# 07_Connector.net
KiCad netlist of a schematic drawn in Altium Designer
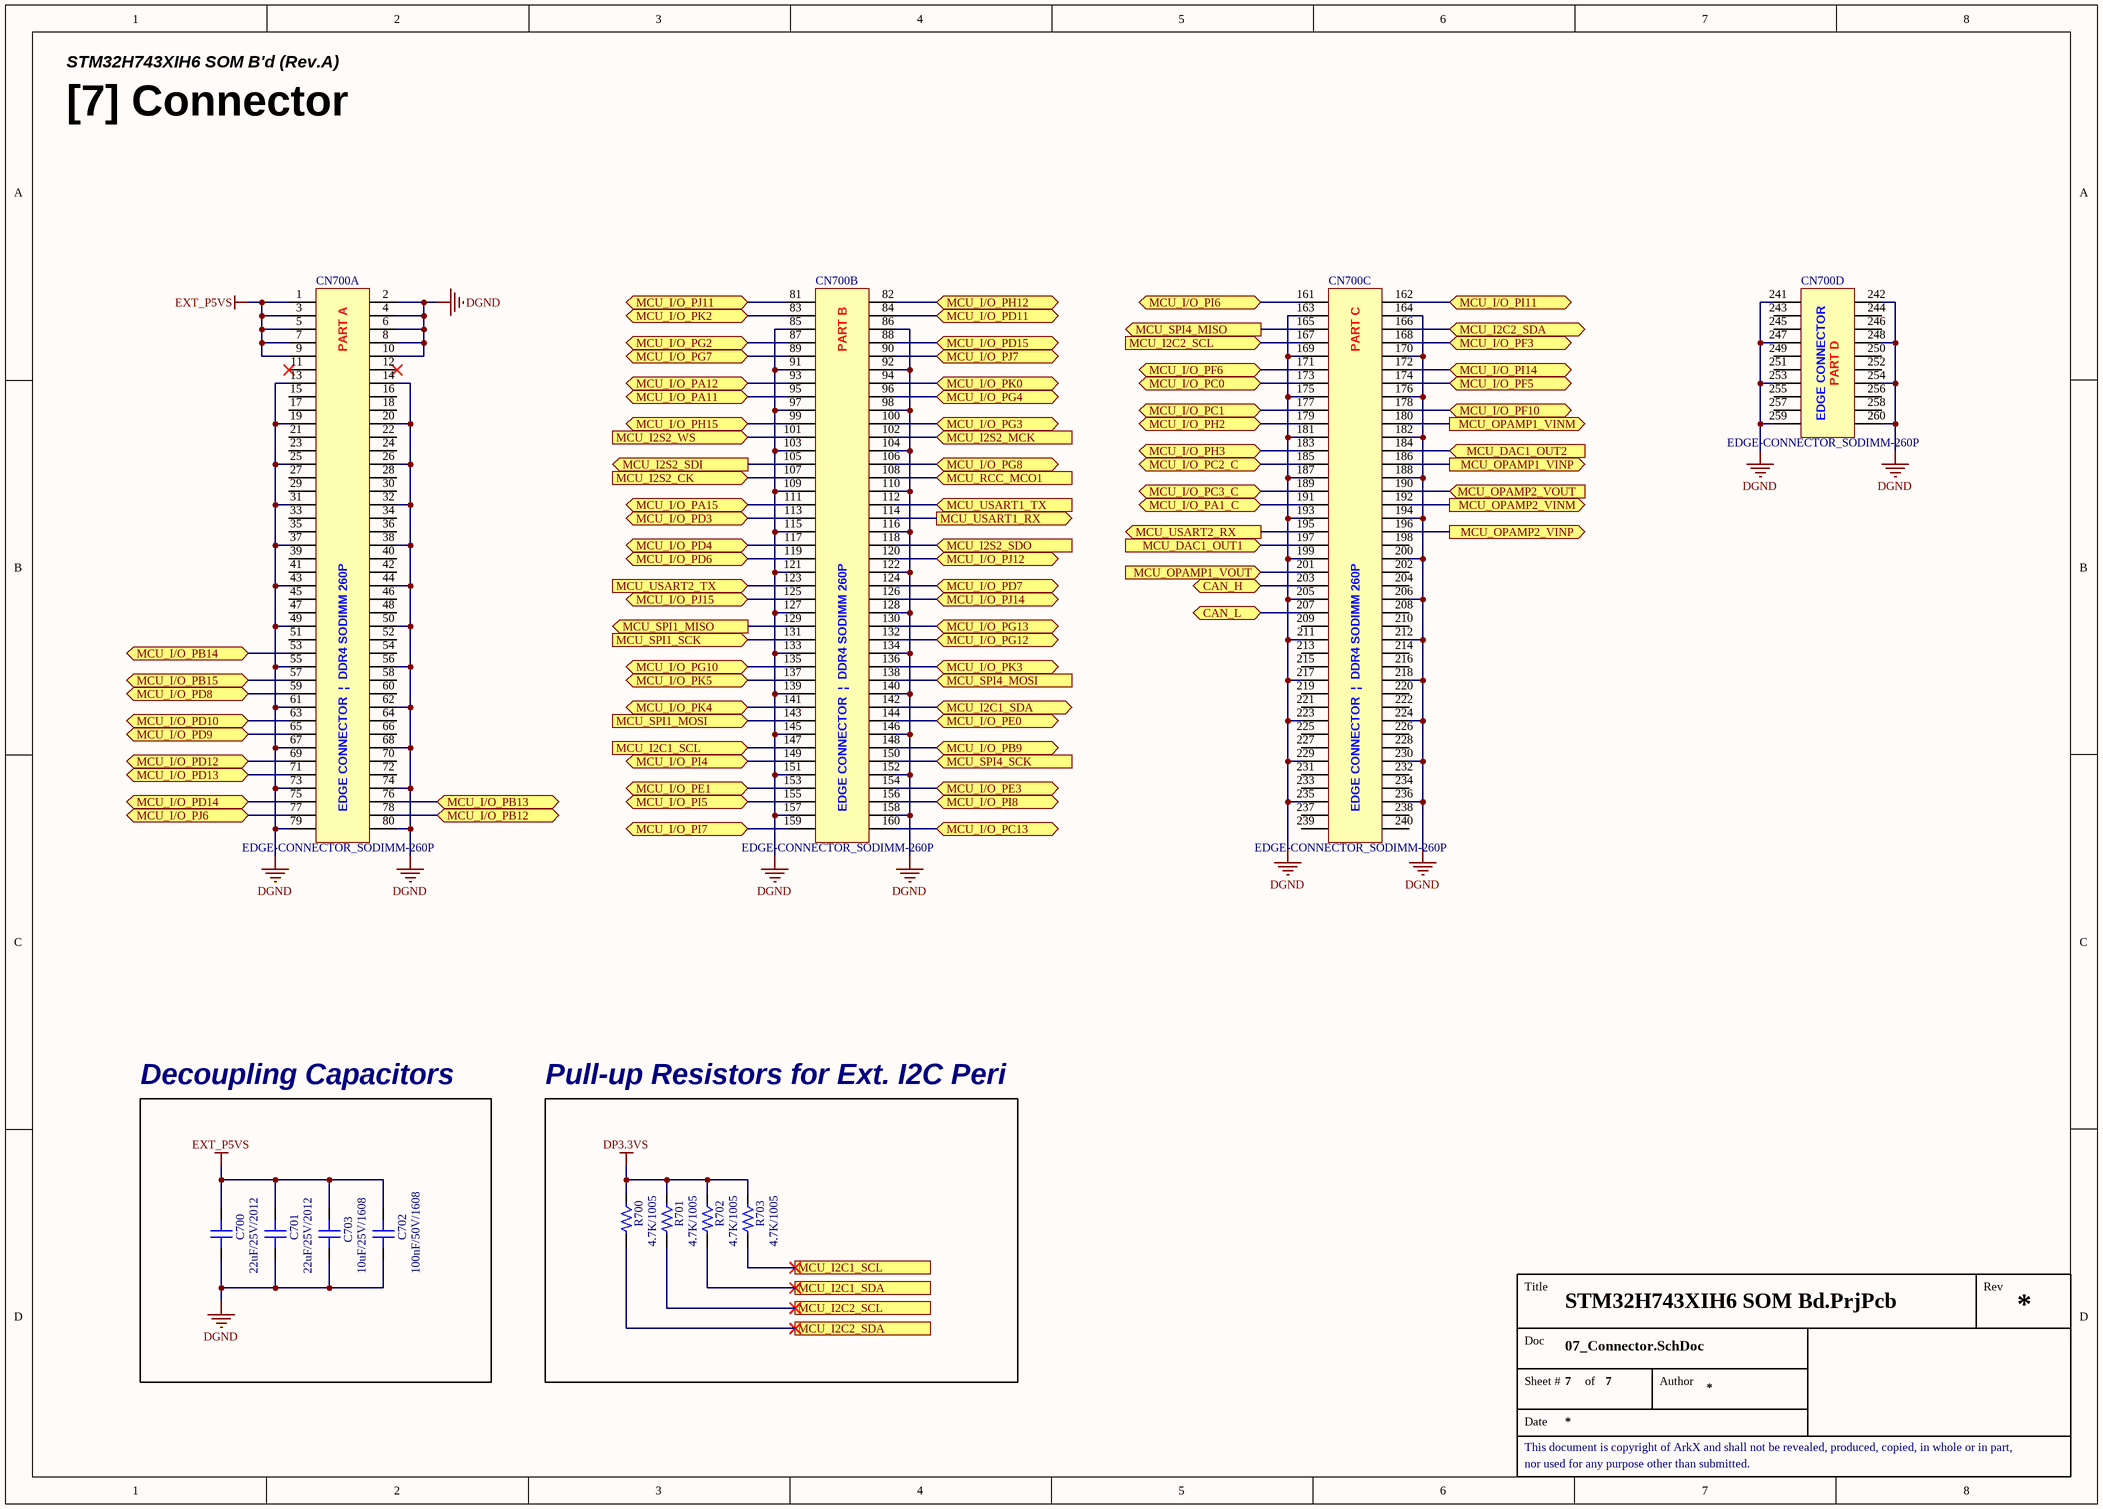
[diagram p0: 07_Connector.SchDoc]

(export (version "E")
  (design (tool "Eeschema 10.0.6"))
  (components
    (comp (ref "C700")
      (value "22uF/25V/2012")
      (footprint "CAP 2012 (0805_INCH)")
      (description "Ceramic CAP_22uF/25V/2012")
      (fields (field (name "LCSC PART #") "C45783"))
      (libsource (lib "Arkx") (part "CAP_22uF/25V/2012"))
    )
    (comp (ref "C701")
      (value "22uF/25V/2012")
      (footprint "CAP 2012 (0805_INCH)")
      (description "Ceramic CAP_22uF/25V/2012")
      (fields (field (name "LCSC PART #") "C45783"))
      (libsource (lib "Arkx") (part "CAP_22uF/25V/2012"))
    )
    (comp (ref "C702")
      (value "100nF/50V/1608")
      (footprint "CAP 1608 (0603_INCH)")
      (description "Ceramic CAP_100nF/50V/1608")
      (fields (field (name "LCSC PART #") "C14663"))
      (libsource (lib "Arkx") (part "CAP_100nF/50V/1608"))
    )
    (comp (ref "C703")
      (value "10uF/25V/1608")
      (footprint "CAP 1608 (0603_INCH)")
      (description "Ceramic CAP_10uF/25V/1608")
      (fields (field (name "LCSC PART #") "C96446"))
      (libsource (lib "Arkx") (part "CAP_10uF/25V/1608"))
    )
    (comp (ref "CN700")
      (value "EDGE-CONNECTOR_SODIMM-260P")
      (footprint "CON_EDGE-CONNECTOR_DDR4-SODIMM-260P")
      (description "EDGE-CONNECTOR_DDR4-SODIMM-260P")
      (fields (field (name "MATING PART NUMBER") "2309409-1"))
      (libsource (lib "Arkx") (part "CON_EDGE-CONNECTOR_DDR4-SODIMM-260P"))
    )
    (comp (ref "R700")
      (value "4.7K/1005")
      (footprint "RES 1005 (0402_inch)")
      (description "RES_4.7K/1005/62.5mW")
      (fields (field (name "LCSC PART #") "C25900"))
      (libsource (lib "Arkx") (part "RES_4.7K/1005/62.5mW"))
    )
    (comp (ref "R701")
      (value "4.7K/1005")
      (footprint "RES 1005 (0402_inch)")
      (description "RES_4.7K/1005/62.5mW")
      (fields (field (name "LCSC PART #") "C25900"))
      (libsource (lib "Arkx") (part "RES_4.7K/1005/62.5mW"))
    )
    (comp (ref "R702")
      (value "4.7K/1005")
      (footprint "RES 1005 (0402_inch)")
      (description "RES_4.7K/1005/62.5mW")
      (fields (field (name "LCSC PART #") "C25900"))
      (libsource (lib "Arkx") (part "RES_4.7K/1005/62.5mW"))
    )
    (comp (ref "R703")
      (value "4.7K/1005")
      (footprint "RES 1005 (0402_inch)")
      (description "RES_4.7K/1005/62.5mW")
      (fields (field (name "LCSC PART #") "C25900"))
      (libsource (lib "Arkx") (part "RES_4.7K/1005/62.5mW"))
    )
  )
  (nets
    (net (code "1") (name "/CAN_H") (class "Default")
      (node (ref "CN700") (pin "203") (pinfunction "203_203") (pintype "passive"))
    )
    (net (code "2") (name "/CAN_L") (class "Default")
      (node (ref "CN700") (pin "207") (pinfunction "207_207") (pintype "passive"))
    )
    (net (code "3") (name "/MCU_DAC1_OUT1") (class "Default")
      (node (ref "CN700") (pin "197") (pinfunction "197_197") (pintype "passive"))
    )
    (net (code "4") (name "/MCU_DAC1_OUT2") (class "Default")
      (node (ref "CN700") (pin "184") (pinfunction "184_184") (pintype "passive"))
    )
    (net (code "5") (name "/MCU_I2C1_SCL") (class "Default")
      (node (ref "CN700") (pin "147") (pinfunction "147_147") (pintype "passive"))
      (node (ref "R703") (pin "2") (pinfunction "2_2") (pintype "passive"))
    )
    (net (code "6") (name "/MCU_I2C1_SDA") (class "Default")
      (node (ref "CN700") (pin "142") (pinfunction "142_142") (pintype "passive"))
      (node (ref "R702") (pin "2") (pinfunction "2_2") (pintype "passive"))
    )
    (net (code "7") (name "/MCU_I2C2_SCL") (class "Default")
      (node (ref "CN700") (pin "167") (pinfunction "167_167") (pintype "passive"))
      (node (ref "R701") (pin "2") (pinfunction "2_2") (pintype "passive"))
    )
    (net (code "8") (name "/MCU_I2C2_SDA") (class "Default")
      (node (ref "CN700") (pin "166") (pinfunction "166_166") (pintype "passive"))
      (node (ref "R700") (pin "2") (pinfunction "2_2") (pintype "passive"))
    )
    (net (code "9") (name "/MCU_I2S2_CK") (class "Default")
      (node (ref "CN700") (pin "107") (pinfunction "107_107") (pintype "passive"))
    )
    (net (code "10") (name "/MCU_I2S2_MCK") (class "Default")
      (node (ref "CN700") (pin "102") (pinfunction "102_102") (pintype "passive"))
    )
    (net (code "11") (name "/MCU_I2S2_SDI") (class "Default")
      (node (ref "CN700") (pin "105") (pinfunction "105_105") (pintype "passive"))
    )
    (net (code "12") (name "/MCU_I2S2_SDO") (class "Default")
      (node (ref "CN700") (pin "118") (pinfunction "118_118") (pintype "passive"))
    )
    (net (code "13") (name "/MCU_I2S2_WS") (class "Default")
      (node (ref "CN700") (pin "101") (pinfunction "101_101") (pintype "passive"))
    )
    (net (code "14") (name "/MCU_I{slash}O_PA1_C") (class "Default")
      (node (ref "CN700") (pin "191") (pinfunction "191_191") (pintype "passive"))
    )
    (net (code "15") (name "/MCU_I{slash}O_PA11") (class "Default")
      (node (ref "CN700") (pin "95") (pinfunction "95_95") (pintype "passive"))
    )
    (net (code "16") (name "/MCU_I{slash}O_PA12") (class "Default")
      (node (ref "CN700") (pin "93") (pinfunction "93_93") (pintype "passive"))
    )
    (net (code "17") (name "/MCU_I{slash}O_PA15") (class "Default")
      (node (ref "CN700") (pin "111") (pinfunction "111_111") (pintype "passive"))
    )
    (net (code "18") (name "/MCU_I{slash}O_PB9") (class "Default")
      (node (ref "CN700") (pin "148") (pinfunction "148_148") (pintype "passive"))
    )
    (net (code "19") (name "/MCU_I{slash}O_PB12") (class "Default")
      (node (ref "CN700") (pin "78") (pinfunction "78_78") (pintype "passive"))
    )
    (net (code "20") (name "/MCU_I{slash}O_PB13") (class "Default")
      (node (ref "CN700") (pin "76") (pinfunction "76_76") (pintype "passive"))
    )
    (net (code "21") (name "/MCU_I{slash}O_PB14") (class "Default")
      (node (ref "CN700") (pin "53") (pinfunction "53_53") (pintype "passive"))
    )
    (net (code "22") (name "/MCU_I{slash}O_PB15") (class "Default")
      (node (ref "CN700") (pin "57") (pinfunction "57_57") (pintype "passive"))
    )
    (net (code "23") (name "/MCU_I{slash}O_PC0") (class "Default")
      (node (ref "CN700") (pin "173") (pinfunction "173_173") (pintype "passive"))
    )
    (net (code "24") (name "/MCU_I{slash}O_PC1") (class "Default")
      (node (ref "CN700") (pin "177") (pinfunction "177_177") (pintype "passive"))
    )
    (net (code "25") (name "/MCU_I{slash}O_PC2_C") (class "Default")
      (node (ref "CN700") (pin "185") (pinfunction "185_185") (pintype "passive"))
    )
    (net (code "26") (name "/MCU_I{slash}O_PC3_C") (class "Default")
      (node (ref "CN700") (pin "189") (pinfunction "189_189") (pintype "passive"))
    )
    (net (code "27") (name "/MCU_I{slash}O_PC13") (class "Default")
      (node (ref "CN700") (pin "160") (pinfunction "160_160") (pintype "passive"))
    )
    (net (code "28") (name "/MCU_I{slash}O_PD3") (class "Default")
      (node (ref "CN700") (pin "113") (pinfunction "113_113") (pintype "passive"))
    )
    (net (code "29") (name "/MCU_I{slash}O_PD4") (class "Default")
      (node (ref "CN700") (pin "117") (pinfunction "117_117") (pintype "passive"))
    )
    (net (code "30") (name "/MCU_I{slash}O_PD6") (class "Default")
      (node (ref "CN700") (pin "119") (pinfunction "119_119") (pintype "passive"))
    )
    (net (code "31") (name "/MCU_I{slash}O_PD7") (class "Default")
      (node (ref "CN700") (pin "124") (pinfunction "124_124") (pintype "passive"))
    )
    (net (code "32") (name "/MCU_I{slash}O_PD8") (class "Default")
      (node (ref "CN700") (pin "59") (pinfunction "59_59") (pintype "passive"))
    )
    (net (code "33") (name "/MCU_I{slash}O_PD9") (class "Default")
      (node (ref "CN700") (pin "65") (pinfunction "65_65") (pintype "passive"))
    )
    (net (code "34") (name "/MCU_I{slash}O_PD10") (class "Default")
      (node (ref "CN700") (pin "63") (pinfunction "63_63") (pintype "passive"))
    )
    (net (code "35") (name "/MCU_I{slash}O_PD11") (class "Default")
      (node (ref "CN700") (pin "84") (pinfunction "84_84") (pintype "passive"))
    )
    (net (code "36") (name "/MCU_I{slash}O_PD12") (class "Default")
      (node (ref "CN700") (pin "69") (pinfunction "69_69") (pintype "passive"))
    )
    (net (code "37") (name "/MCU_I{slash}O_PD13") (class "Default")
      (node (ref "CN700") (pin "71") (pinfunction "71_71") (pintype "passive"))
    )
    (net (code "38") (name "/MCU_I{slash}O_PD14") (class "Default")
      (node (ref "CN700") (pin "75") (pinfunction "75_75") (pintype "passive"))
    )
    (net (code "39") (name "/MCU_I{slash}O_PD15") (class "Default")
      (node (ref "CN700") (pin "88") (pinfunction "88_88") (pintype "passive"))
    )
    (net (code "40") (name "/MCU_I{slash}O_PE0") (class "Default")
      (node (ref "CN700") (pin "144") (pinfunction "144_144") (pintype "passive"))
    )
    (net (code "41") (name "/MCU_I{slash}O_PE1") (class "Default")
      (node (ref "CN700") (pin "153") (pinfunction "153_153") (pintype "passive"))
    )
    (net (code "42") (name "/MCU_I{slash}O_PE3") (class "Default")
      (node (ref "CN700") (pin "154") (pinfunction "154_154") (pintype "passive"))
    )
    (net (code "43") (name "/MCU_I{slash}O_PF3") (class "Default")
      (node (ref "CN700") (pin "168") (pinfunction "168_168") (pintype "passive"))
    )
    (net (code "44") (name "/MCU_I{slash}O_PF5") (class "Default")
      (node (ref "CN700") (pin "174") (pinfunction "174_174") (pintype "passive"))
    )
    (net (code "45") (name "/MCU_I{slash}O_PF6") (class "Default")
      (node (ref "CN700") (pin "171") (pinfunction "171_171") (pintype "passive"))
    )
    (net (code "46") (name "/MCU_I{slash}O_PF10") (class "Default")
      (node (ref "CN700") (pin "178") (pinfunction "178_178") (pintype "passive"))
    )
    (net (code "47") (name "/MCU_I{slash}O_PG2") (class "Default")
      (node (ref "CN700") (pin "87") (pinfunction "87_87") (pintype "passive"))
    )
    (net (code "48") (name "/MCU_I{slash}O_PG3") (class "Default")
      (node (ref "CN700") (pin "100") (pinfunction "100_100") (pintype "passive"))
    )
    (net (code "49") (name "/MCU_I{slash}O_PG4") (class "Default")
      (node (ref "CN700") (pin "96") (pinfunction "96_96") (pintype "passive"))
    )
    (net (code "50") (name "/MCU_I{slash}O_PG7") (class "Default")
      (node (ref "CN700") (pin "89") (pinfunction "89_89") (pintype "passive"))
    )
    (net (code "51") (name "/MCU_I{slash}O_PG8") (class "Default")
      (node (ref "CN700") (pin "106") (pinfunction "106_106") (pintype "passive"))
    )
    (net (code "52") (name "/MCU_I{slash}O_PG10") (class "Default")
      (node (ref "CN700") (pin "135") (pinfunction "135_135") (pintype "passive"))
    )
    (net (code "53") (name "/MCU_I{slash}O_PG12") (class "Default")
      (node (ref "CN700") (pin "132") (pinfunction "132_132") (pintype "passive"))
    )
    (net (code "54") (name "/MCU_I{slash}O_PG13") (class "Default")
      (node (ref "CN700") (pin "130") (pinfunction "130_130") (pintype "passive"))
    )
    (net (code "55") (name "/MCU_I{slash}O_PH2") (class "Default")
      (node (ref "CN700") (pin "179") (pinfunction "179_179") (pintype "passive"))
    )
    (net (code "56") (name "/MCU_I{slash}O_PH3") (class "Default")
      (node (ref "CN700") (pin "183") (pinfunction "183_183") (pintype "passive"))
    )
    (net (code "57") (name "/MCU_I{slash}O_PH12") (class "Default")
      (node (ref "CN700") (pin "82") (pinfunction "82_82") (pintype "passive"))
    )
    (net (code "58") (name "/MCU_I{slash}O_PH15") (class "Default")
      (node (ref "CN700") (pin "99") (pinfunction "99_99") (pintype "passive"))
    )
    (net (code "59") (name "/MCU_I{slash}O_PI4") (class "Default")
      (node (ref "CN700") (pin "149") (pinfunction "149_149") (pintype "passive"))
    )
    (net (code "60") (name "/MCU_I{slash}O_PI5") (class "Default")
      (node (ref "CN700") (pin "155") (pinfunction "155_155") (pintype "passive"))
    )
    (net (code "61") (name "/MCU_I{slash}O_PI6") (class "Default")
      (node (ref "CN700") (pin "161") (pinfunction "161_161") (pintype "passive"))
    )
    (net (code "62") (name "/MCU_I{slash}O_PI7") (class "Default")
      (node (ref "CN700") (pin "159") (pinfunction "159_159") (pintype "passive"))
    )
    (net (code "63") (name "/MCU_I{slash}O_PI8") (class "Default")
      (node (ref "CN700") (pin "156") (pinfunction "156_156") (pintype "passive"))
    )
    (net (code "64") (name "/MCU_I{slash}O_PI11") (class "Default")
      (node (ref "CN700") (pin "162") (pinfunction "162_162") (pintype "passive"))
    )
    (net (code "65") (name "/MCU_I{slash}O_PI14") (class "Default")
      (node (ref "CN700") (pin "172") (pinfunction "172_172") (pintype "passive"))
    )
    (net (code "66") (name "/MCU_I{slash}O_PJ6") (class "Default")
      (node (ref "CN700") (pin "77") (pinfunction "77_77") (pintype "passive"))
    )
    (net (code "67") (name "/MCU_I{slash}O_PJ7") (class "Default")
      (node (ref "CN700") (pin "90") (pinfunction "90_90") (pintype "passive"))
    )
    (net (code "68") (name "/MCU_I{slash}O_PJ11") (class "Default")
      (node (ref "CN700") (pin "81") (pinfunction "81_81") (pintype "passive"))
    )
    (net (code "69") (name "/MCU_I{slash}O_PJ12") (class "Default")
      (node (ref "CN700") (pin "120") (pinfunction "120_120") (pintype "passive"))
    )
    (net (code "70") (name "/MCU_I{slash}O_PJ14") (class "Default")
      (node (ref "CN700") (pin "126") (pinfunction "126_126") (pintype "passive"))
    )
    (net (code "71") (name "/MCU_I{slash}O_PJ15") (class "Default")
      (node (ref "CN700") (pin "125") (pinfunction "125_125") (pintype "passive"))
    )
    (net (code "72") (name "/MCU_I{slash}O_PK0") (class "Default")
      (node (ref "CN700") (pin "94") (pinfunction "94_94") (pintype "passive"))
    )
    (net (code "73") (name "/MCU_I{slash}O_PK2") (class "Default")
      (node (ref "CN700") (pin "83") (pinfunction "83_83") (pintype "passive"))
    )
    (net (code "74") (name "/MCU_I{slash}O_PK3") (class "Default")
      (node (ref "CN700") (pin "136") (pinfunction "136_136") (pintype "passive"))
    )
    (net (code "75") (name "/MCU_I{slash}O_PK4") (class "Default")
      (node (ref "CN700") (pin "141") (pinfunction "141_141") (pintype "passive"))
    )
    (net (code "76") (name "/MCU_I{slash}O_PK5") (class "Default")
      (node (ref "CN700") (pin "137") (pinfunction "137_137") (pintype "passive"))
    )
    (net (code "77") (name "/MCU_OPAMP1_VINM") (class "Default")
      (node (ref "CN700") (pin "180") (pinfunction "180_180") (pintype "passive"))
    )
    (net (code "78") (name "/MCU_OPAMP1_VINP") (class "Default")
      (node (ref "CN700") (pin "186") (pinfunction "186_186") (pintype "passive"))
    )
    (net (code "79") (name "/MCU_OPAMP1_VOUT") (class "Default")
      (node (ref "CN700") (pin "201") (pinfunction "201_201") (pintype "passive"))
    )
    (net (code "80") (name "/MCU_OPAMP2_VINM") (class "Default")
      (node (ref "CN700") (pin "192") (pinfunction "192_192") (pintype "passive"))
    )
    (net (code "81") (name "/MCU_OPAMP2_VINP") (class "Default")
      (node (ref "CN700") (pin "196") (pinfunction "196_196") (pintype "passive"))
    )
    (net (code "82") (name "/MCU_OPAMP2_VOUT") (class "Default")
      (node (ref "CN700") (pin "190") (pinfunction "190_190") (pintype "passive"))
    )
    (net (code "83") (name "/MCU_RCC_MCO1") (class "Default")
      (node (ref "CN700") (pin "108") (pinfunction "108_108") (pintype "passive"))
    )
    (net (code "84") (name "/MCU_SPI1_MISO") (class "Default")
      (node (ref "CN700") (pin "129") (pinfunction "129_129") (pintype "passive"))
    )
    (net (code "85") (name "/MCU_SPI1_MOSI") (class "Default")
      (node (ref "CN700") (pin "143") (pinfunction "143_143") (pintype "passive"))
    )
    (net (code "86") (name "/MCU_SPI1_SCK") (class "Default")
      (node (ref "CN700") (pin "131") (pinfunction "131_131") (pintype "passive"))
    )
    (net (code "87") (name "/MCU_SPI4_MISO") (class "Default")
      (node (ref "CN700") (pin "165") (pinfunction "165_165") (pintype "passive"))
    )
    (net (code "88") (name "/MCU_SPI4_MOSI") (class "Default")
      (node (ref "CN700") (pin "138") (pinfunction "138_138") (pintype "passive"))
    )
    (net (code "89") (name "/MCU_SPI4_SCK") (class "Default")
      (node (ref "CN700") (pin "150") (pinfunction "150_150") (pintype "passive"))
    )
    (net (code "90") (name "/MCU_USART1_RX") (class "Default")
      (node (ref "CN700") (pin "114") (pinfunction "114_114") (pintype "passive"))
    )
    (net (code "91") (name "/MCU_USART1_TX") (class "Default")
      (node (ref "CN700") (pin "112") (pinfunction "112_112") (pintype "passive"))
    )
    (net (code "92") (name "/MCU_USART2_RX") (class "Default")
      (node (ref "CN700") (pin "195") (pinfunction "195_195") (pintype "passive"))
    )
    (net (code "93") (name "/MCU_USART2_TX") (class "Default")
      (node (ref "CN700") (pin "123") (pinfunction "123_123") (pintype "passive"))
    )
    (net (code "94") (name "DGND") (class "Default")
      (node (ref "C700") (pin "1") (pinfunction "1_1") (pintype "passive"))
      (node (ref "C701") (pin "1") (pinfunction "1_1") (pintype "passive"))
      (node (ref "C702") (pin "1") (pinfunction "1_1") (pintype "passive"))
      (node (ref "C703") (pin "1") (pinfunction "1_1") (pintype "passive"))
      (node (ref "CN700") (pin "10") (pinfunction "10_10") (pintype "passive"))
      (node (ref "CN700") (pin "103") (pinfunction "103_103") (pintype "passive"))
      (node (ref "CN700") (pin "104") (pinfunction "104_104") (pintype "passive"))
      (node (ref "CN700") (pin "109") (pinfunction "109_109") (pintype "passive"))
      (node (ref "CN700") (pin "110") (pinfunction "110_110") (pintype "passive"))
      (node (ref "CN700") (pin "115") (pinfunction "115_115") (pintype "passive"))
      (node (ref "CN700") (pin "116") (pinfunction "116_116") (pintype "passive"))
      (node (ref "CN700") (pin "121") (pinfunction "121_121") (pintype "passive"))
      (node (ref "CN700") (pin "122") (pinfunction "122_122") (pintype "passive"))
      (node (ref "CN700") (pin "127") (pinfunction "127_127") (pintype "passive"))
      (node (ref "CN700") (pin "128") (pinfunction "128_128") (pintype "passive"))
      (node (ref "CN700") (pin "13") (pinfunction "13_13") (pintype "passive"))
      (node (ref "CN700") (pin "133") (pinfunction "133_133") (pintype "passive"))
      (node (ref "CN700") (pin "134") (pinfunction "134_134") (pintype "passive"))
      (node (ref "CN700") (pin "139") (pinfunction "139_139") (pintype "passive"))
      (node (ref "CN700") (pin "14") (pinfunction "14_14") (pintype "passive"))
      (node (ref "CN700") (pin "140") (pinfunction "140_140") (pintype "passive"))
      (node (ref "CN700") (pin "145") (pinfunction "145_145") (pintype "passive"))
      (node (ref "CN700") (pin "146") (pinfunction "146_146") (pintype "passive"))
      (node (ref "CN700") (pin "151") (pinfunction "151_151") (pintype "passive"))
      (node (ref "CN700") (pin "152") (pinfunction "152_152") (pintype "passive"))
      (node (ref "CN700") (pin "157") (pinfunction "157_157") (pintype "passive"))
      (node (ref "CN700") (pin "158") (pinfunction "158_158") (pintype "passive"))
      (node (ref "CN700") (pin "163") (pinfunction "163_163") (pintype "passive"))
      (node (ref "CN700") (pin "164") (pinfunction "164_164") (pintype "passive"))
      (node (ref "CN700") (pin "169") (pinfunction "169_169") (pintype "passive"))
      (node (ref "CN700") (pin "170") (pinfunction "170_170") (pintype "passive"))
      (node (ref "CN700") (pin "175") (pinfunction "175_175") (pintype "passive"))
      (node (ref "CN700") (pin "176") (pinfunction "176_176") (pintype "passive"))
      (node (ref "CN700") (pin "181") (pinfunction "181_181") (pintype "passive"))
      (node (ref "CN700") (pin "182") (pinfunction "182_182") (pintype "passive"))
      (node (ref "CN700") (pin "187") (pinfunction "187_187") (pintype "passive"))
      (node (ref "CN700") (pin "188") (pinfunction "188_188") (pintype "passive"))
      (node (ref "CN700") (pin "19") (pinfunction "19_19") (pintype "passive"))
      (node (ref "CN700") (pin "193") (pinfunction "193_193") (pintype "passive"))
      (node (ref "CN700") (pin "194") (pinfunction "194_194") (pintype "passive"))
      (node (ref "CN700") (pin "199") (pinfunction "199_199") (pintype "passive"))
      (node (ref "CN700") (pin "2") (pinfunction "2_2") (pintype "passive"))
      (node (ref "CN700") (pin "20") (pinfunction "20_20") (pintype "passive"))
      (node (ref "CN700") (pin "200") (pinfunction "200_200") (pintype "passive"))
      (node (ref "CN700") (pin "205") (pinfunction "205_205") (pintype "passive"))
      (node (ref "CN700") (pin "206") (pinfunction "206_206") (pintype "passive"))
      (node (ref "CN700") (pin "211") (pinfunction "211_211") (pintype "passive"))
      (node (ref "CN700") (pin "212") (pinfunction "212_212") (pintype "passive"))
      (node (ref "CN700") (pin "217") (pinfunction "217_217") (pintype "passive"))
      (node (ref "CN700") (pin "218") (pinfunction "218_218") (pintype "passive"))
      (node (ref "CN700") (pin "223") (pinfunction "223_223") (pintype "passive"))
      (node (ref "CN700") (pin "224") (pinfunction "224_224") (pintype "passive"))
      (node (ref "CN700") (pin "229") (pinfunction "229_229") (pintype "passive"))
      (node (ref "CN700") (pin "230") (pinfunction "230_230") (pintype "passive"))
      (node (ref "CN700") (pin "235") (pinfunction "235_235") (pintype "passive"))
      (node (ref "CN700") (pin "236") (pinfunction "236_236") (pintype "passive"))
      (node (ref "CN700") (pin "241") (pinfunction "241_241") (pintype "passive"))
      (node (ref "CN700") (pin "242") (pinfunction "242_242") (pintype "passive"))
      (node (ref "CN700") (pin "247") (pinfunction "247_247") (pintype "passive"))
      (node (ref "CN700") (pin "248") (pinfunction "248_248") (pintype "passive"))
      (node (ref "CN700") (pin "25") (pinfunction "25_25") (pintype "passive"))
      (node (ref "CN700") (pin "253") (pinfunction "253_253") (pintype "passive"))
      (node (ref "CN700") (pin "254") (pinfunction "254_254") (pintype "passive"))
      (node (ref "CN700") (pin "259") (pinfunction "259_259") (pintype "passive"))
      (node (ref "CN700") (pin "26") (pinfunction "26_26") (pintype "passive"))
      (node (ref "CN700") (pin "260") (pinfunction "260_260") (pintype "passive"))
      (node (ref "CN700") (pin "31") (pinfunction "31_31") (pintype "passive"))
      (node (ref "CN700") (pin "32") (pinfunction "32_32") (pintype "passive"))
      (node (ref "CN700") (pin "37") (pinfunction "37_37") (pintype "passive"))
      (node (ref "CN700") (pin "38") (pinfunction "38_38") (pintype "passive"))
      (node (ref "CN700") (pin "4") (pinfunction "4_4") (pintype "passive"))
      (node (ref "CN700") (pin "43") (pinfunction "43_43") (pintype "passive"))
      (node (ref "CN700") (pin "44") (pinfunction "44_44") (pintype "passive"))
      (node (ref "CN700") (pin "49") (pinfunction "49_49") (pintype "passive"))
      (node (ref "CN700") (pin "50") (pinfunction "50_50") (pintype "passive"))
      (node (ref "CN700") (pin "55") (pinfunction "55_55") (pintype "passive"))
      (node (ref "CN700") (pin "56") (pinfunction "56_56") (pintype "passive"))
      (node (ref "CN700") (pin "6") (pinfunction "6_6") (pintype "passive"))
      (node (ref "CN700") (pin "61") (pinfunction "61_61") (pintype "passive"))
      (node (ref "CN700") (pin "62") (pinfunction "62_62") (pintype "passive"))
      (node (ref "CN700") (pin "67") (pinfunction "67_67") (pintype "passive"))
      (node (ref "CN700") (pin "68") (pinfunction "68_68") (pintype "passive"))
      (node (ref "CN700") (pin "73") (pinfunction "73_73") (pintype "passive"))
      (node (ref "CN700") (pin "74") (pinfunction "74_74") (pintype "passive"))
      (node (ref "CN700") (pin "79") (pinfunction "79_79") (pintype "passive"))
      (node (ref "CN700") (pin "8") (pinfunction "8_8") (pintype "passive"))
      (node (ref "CN700") (pin "80") (pinfunction "80_80") (pintype "passive"))
      (node (ref "CN700") (pin "85") (pinfunction "85_85") (pintype "passive"))
      (node (ref "CN700") (pin "86") (pinfunction "86_86") (pintype "passive"))
      (node (ref "CN700") (pin "91") (pinfunction "91_91") (pintype "passive"))
      (node (ref "CN700") (pin "92") (pinfunction "92_92") (pintype "passive"))
      (node (ref "CN700") (pin "97") (pinfunction "97_97") (pintype "passive"))
      (node (ref "CN700") (pin "98") (pinfunction "98_98") (pintype "passive"))
    )
    (net (code "95") (name "DP3.3VS") (class "Default")
      (node (ref "R700") (pin "1") (pinfunction "1_1") (pintype "passive"))
      (node (ref "R701") (pin "1") (pinfunction "1_1") (pintype "passive"))
      (node (ref "R702") (pin "1") (pinfunction "1_1") (pintype "passive"))
      (node (ref "R703") (pin "1") (pinfunction "1_1") (pintype "passive"))
    )
    (net (code "96") (name "EXT_P5VS") (class "Default")
      (node (ref "C700") (pin "2") (pinfunction "2_2") (pintype "passive"))
      (node (ref "C701") (pin "2") (pinfunction "2_2") (pintype "passive"))
      (node (ref "C702") (pin "2") (pinfunction "2_2") (pintype "passive"))
      (node (ref "C703") (pin "2") (pinfunction "2_2") (pintype "passive"))
      (node (ref "CN700") (pin "1") (pinfunction "1_1") (pintype "passive"))
      (node (ref "CN700") (pin "3") (pinfunction "3_3") (pintype "passive"))
      (node (ref "CN700") (pin "5") (pinfunction "5_5") (pintype "passive"))
      (node (ref "CN700") (pin "7") (pinfunction "7_7") (pintype "passive"))
      (node (ref "CN700") (pin "9") (pinfunction "9_9") (pintype "passive"))
    )
    (net (code "97") (name "unconnected-(CN700-Pad11)") (class "Default")
      (node (ref "CN700") (pin "11") (pinfunction "11_11") (pintype "passive+no_connect"))
    )
    (net (code "98") (name "unconnected-(CN700-Pad12)") (class "Default")
      (node (ref "CN700") (pin "12") (pinfunction "12_12") (pintype "passive+no_connect"))
    )
    (net (code "99") (name "unconnected-(CN700-Pad15)") (class "Default")
      (node (ref "CN700") (pin "15") (pinfunction "15_15") (pintype "passive"))
    )
    (net (code "100") (name "unconnected-(CN700-Pad16)") (class "Default")
      (node (ref "CN700") (pin "16") (pinfunction "16_16") (pintype "passive"))
    )
    (net (code "101") (name "unconnected-(CN700-Pad17)") (class "Default")
      (node (ref "CN700") (pin "17") (pinfunction "17_17") (pintype "passive"))
    )
    (net (code "102") (name "unconnected-(CN700-Pad18)") (class "Default")
      (node (ref "CN700") (pin "18") (pinfunction "18_18") (pintype "passive"))
    )
    (net (code "103") (name "unconnected-(CN700-Pad21)") (class "Default")
      (node (ref "CN700") (pin "21") (pinfunction "21_21") (pintype "passive"))
    )
    (net (code "104") (name "unconnected-(CN700-Pad22)") (class "Default")
      (node (ref "CN700") (pin "22") (pinfunction "22_22") (pintype "passive"))
    )
    (net (code "105") (name "unconnected-(CN700-Pad23)") (class "Default")
      (node (ref "CN700") (pin "23") (pinfunction "23_23") (pintype "passive"))
    )
    (net (code "106") (name "unconnected-(CN700-Pad24)") (class "Default")
      (node (ref "CN700") (pin "24") (pinfunction "24_24") (pintype "passive"))
    )
    (net (code "107") (name "unconnected-(CN700-Pad27)") (class "Default")
      (node (ref "CN700") (pin "27") (pinfunction "27_27") (pintype "passive"))
    )
    (net (code "108") (name "unconnected-(CN700-Pad28)") (class "Default")
      (node (ref "CN700") (pin "28") (pinfunction "28_28") (pintype "passive"))
    )
    (net (code "109") (name "unconnected-(CN700-Pad29)") (class "Default")
      (node (ref "CN700") (pin "29") (pinfunction "29_29") (pintype "passive"))
    )
    (net (code "110") (name "unconnected-(CN700-Pad30)") (class "Default")
      (node (ref "CN700") (pin "30") (pinfunction "30_30") (pintype "passive"))
    )
    (net (code "111") (name "unconnected-(CN700-Pad33)") (class "Default")
      (node (ref "CN700") (pin "33") (pinfunction "33_33") (pintype "passive"))
    )
    (net (code "112") (name "unconnected-(CN700-Pad34)") (class "Default")
      (node (ref "CN700") (pin "34") (pinfunction "34_34") (pintype "passive"))
    )
    (net (code "113") (name "unconnected-(CN700-Pad35)") (class "Default")
      (node (ref "CN700") (pin "35") (pinfunction "35_35") (pintype "passive"))
    )
    (net (code "114") (name "unconnected-(CN700-Pad36)") (class "Default")
      (node (ref "CN700") (pin "36") (pinfunction "36_36") (pintype "passive"))
    )
    (net (code "115") (name "unconnected-(CN700-Pad39)") (class "Default")
      (node (ref "CN700") (pin "39") (pinfunction "39_39") (pintype "passive"))
    )
    (net (code "116") (name "unconnected-(CN700-Pad40)") (class "Default")
      (node (ref "CN700") (pin "40") (pinfunction "40_40") (pintype "passive"))
    )
    (net (code "117") (name "unconnected-(CN700-Pad41)") (class "Default")
      (node (ref "CN700") (pin "41") (pinfunction "41_41") (pintype "passive"))
    )
    (net (code "118") (name "unconnected-(CN700-Pad42)") (class "Default")
      (node (ref "CN700") (pin "42") (pinfunction "42_42") (pintype "passive"))
    )
    (net (code "119") (name "unconnected-(CN700-Pad45)") (class "Default")
      (node (ref "CN700") (pin "45") (pinfunction "45_45") (pintype "passive"))
    )
    (net (code "120") (name "unconnected-(CN700-Pad46)") (class "Default")
      (node (ref "CN700") (pin "46") (pinfunction "46_46") (pintype "passive"))
    )
    (net (code "121") (name "unconnected-(CN700-Pad47)") (class "Default")
      (node (ref "CN700") (pin "47") (pinfunction "47_47") (pintype "passive"))
    )
    (net (code "122") (name "unconnected-(CN700-Pad48)") (class "Default")
      (node (ref "CN700") (pin "48") (pinfunction "48_48") (pintype "passive"))
    )
    (net (code "123") (name "unconnected-(CN700-Pad51)") (class "Default")
      (node (ref "CN700") (pin "51") (pinfunction "51_51") (pintype "passive"))
    )
    (net (code "124") (name "unconnected-(CN700-Pad52)") (class "Default")
      (node (ref "CN700") (pin "52") (pinfunction "52_52") (pintype "passive"))
    )
    (net (code "125") (name "unconnected-(CN700-Pad54)") (class "Default")
      (node (ref "CN700") (pin "54") (pinfunction "54_54") (pintype "passive"))
    )
    (net (code "126") (name "unconnected-(CN700-Pad58)") (class "Default")
      (node (ref "CN700") (pin "58") (pinfunction "58_58") (pintype "passive"))
    )
    (net (code "127") (name "unconnected-(CN700-Pad60)") (class "Default")
      (node (ref "CN700") (pin "60") (pinfunction "60_60") (pintype "passive"))
    )
    (net (code "128") (name "unconnected-(CN700-Pad64)") (class "Default")
      (node (ref "CN700") (pin "64") (pinfunction "64_64") (pintype "passive"))
    )
    (net (code "129") (name "unconnected-(CN700-Pad66)") (class "Default")
      (node (ref "CN700") (pin "66") (pinfunction "66_66") (pintype "passive"))
    )
    (net (code "130") (name "unconnected-(CN700-Pad70)") (class "Default")
      (node (ref "CN700") (pin "70") (pinfunction "70_70") (pintype "passive"))
    )
    (net (code "131") (name "unconnected-(CN700-Pad72)") (class "Default")
      (node (ref "CN700") (pin "72") (pinfunction "72_72") (pintype "passive"))
    )
    (net (code "132") (name "unconnected-(CN700-Pad198)") (class "Default")
      (node (ref "CN700") (pin "198") (pinfunction "198_198") (pintype "passive"))
    )
    (net (code "133") (name "unconnected-(CN700-Pad202)") (class "Default")
      (node (ref "CN700") (pin "202") (pinfunction "202_202") (pintype "passive"))
    )
    (net (code "134") (name "unconnected-(CN700-Pad204)") (class "Default")
      (node (ref "CN700") (pin "204") (pinfunction "204_204") (pintype "passive"))
    )
    (net (code "135") (name "unconnected-(CN700-Pad208)") (class "Default")
      (node (ref "CN700") (pin "208") (pinfunction "208_208") (pintype "passive"))
    )
    (net (code "136") (name "unconnected-(CN700-Pad209)") (class "Default")
      (node (ref "CN700") (pin "209") (pinfunction "209_209") (pintype "passive"))
    )
    (net (code "137") (name "unconnected-(CN700-Pad210)") (class "Default")
      (node (ref "CN700") (pin "210") (pinfunction "210_210") (pintype "passive"))
    )
    (net (code "138") (name "unconnected-(CN700-Pad213)") (class "Default")
      (node (ref "CN700") (pin "213") (pinfunction "213_213") (pintype "passive"))
    )
    (net (code "139") (name "unconnected-(CN700-Pad214)") (class "Default")
      (node (ref "CN700") (pin "214") (pinfunction "214_214") (pintype "passive"))
    )
    (net (code "140") (name "unconnected-(CN700-Pad215)") (class "Default")
      (node (ref "CN700") (pin "215") (pinfunction "215_215") (pintype "passive"))
    )
    (net (code "141") (name "unconnected-(CN700-Pad216)") (class "Default")
      (node (ref "CN700") (pin "216") (pinfunction "216_216") (pintype "passive"))
    )
    (net (code "142") (name "unconnected-(CN700-Pad219)") (class "Default")
      (node (ref "CN700") (pin "219") (pinfunction "219_219") (pintype "passive"))
    )
    (net (code "143") (name "unconnected-(CN700-Pad220)") (class "Default")
      (node (ref "CN700") (pin "220") (pinfunction "220_220") (pintype "passive"))
    )
    (net (code "144") (name "unconnected-(CN700-Pad221)") (class "Default")
      (node (ref "CN700") (pin "221") (pinfunction "221_221") (pintype "passive"))
    )
    (net (code "145") (name "unconnected-(CN700-Pad222)") (class "Default")
      (node (ref "CN700") (pin "222") (pinfunction "222_222") (pintype "passive"))
    )
    (net (code "146") (name "unconnected-(CN700-Pad225)") (class "Default")
      (node (ref "CN700") (pin "225") (pinfunction "225_225") (pintype "passive"))
    )
    (net (code "147") (name "unconnected-(CN700-Pad226)") (class "Default")
      (node (ref "CN700") (pin "226") (pinfunction "226_226") (pintype "passive"))
    )
    (net (code "148") (name "unconnected-(CN700-Pad227)") (class "Default")
      (node (ref "CN700") (pin "227") (pinfunction "227_227") (pintype "passive"))
    )
    (net (code "149") (name "unconnected-(CN700-Pad228)") (class "Default")
      (node (ref "CN700") (pin "228") (pinfunction "228_228") (pintype "passive"))
    )
    (net (code "150") (name "unconnected-(CN700-Pad231)") (class "Default")
      (node (ref "CN700") (pin "231") (pinfunction "231_231") (pintype "passive"))
    )
    (net (code "151") (name "unconnected-(CN700-Pad232)") (class "Default")
      (node (ref "CN700") (pin "232") (pinfunction "232_232") (pintype "passive"))
    )
    (net (code "152") (name "unconnected-(CN700-Pad233)") (class "Default")
      (node (ref "CN700") (pin "233") (pinfunction "233_233") (pintype "passive"))
    )
    (net (code "153") (name "unconnected-(CN700-Pad234)") (class "Default")
      (node (ref "CN700") (pin "234") (pinfunction "234_234") (pintype "passive"))
    )
    (net (code "154") (name "unconnected-(CN700-Pad237)") (class "Default")
      (node (ref "CN700") (pin "237") (pinfunction "237_237") (pintype "passive"))
    )
    (net (code "155") (name "unconnected-(CN700-Pad238)") (class "Default")
      (node (ref "CN700") (pin "238") (pinfunction "238_238") (pintype "passive"))
    )
    (net (code "156") (name "unconnected-(CN700-Pad239)") (class "Default")
      (node (ref "CN700") (pin "239") (pinfunction "239_239") (pintype "passive"))
    )
    (net (code "157") (name "unconnected-(CN700-Pad240)") (class "Default")
      (node (ref "CN700") (pin "240") (pinfunction "240_240") (pintype "passive"))
    )
    (net (code "158") (name "unconnected-(CN700-Pad243)") (class "Default")
      (node (ref "CN700") (pin "243") (pinfunction "243_243") (pintype "passive"))
    )
    (net (code "159") (name "unconnected-(CN700-Pad244)") (class "Default")
      (node (ref "CN700") (pin "244") (pinfunction "244_244") (pintype "passive"))
    )
    (net (code "160") (name "unconnected-(CN700-Pad245)") (class "Default")
      (node (ref "CN700") (pin "245") (pinfunction "245_245") (pintype "passive"))
    )
    (net (code "161") (name "unconnected-(CN700-Pad246)") (class "Default")
      (node (ref "CN700") (pin "246") (pinfunction "246_246") (pintype "passive"))
    )
    (net (code "162") (name "unconnected-(CN700-Pad249)") (class "Default")
      (node (ref "CN700") (pin "249") (pinfunction "249_249") (pintype "passive"))
    )
    (net (code "163") (name "unconnected-(CN700-Pad250)") (class "Default")
      (node (ref "CN700") (pin "250") (pinfunction "250_250") (pintype "passive"))
    )
    (net (code "164") (name "unconnected-(CN700-Pad251)") (class "Default")
      (node (ref "CN700") (pin "251") (pinfunction "251_251") (pintype "passive"))
    )
    (net (code "165") (name "unconnected-(CN700-Pad252)") (class "Default")
      (node (ref "CN700") (pin "252") (pinfunction "252_252") (pintype "passive"))
    )
    (net (code "166") (name "unconnected-(CN700-Pad255)") (class "Default")
      (node (ref "CN700") (pin "255") (pinfunction "255_255") (pintype "passive"))
    )
    (net (code "167") (name "unconnected-(CN700-Pad256)") (class "Default")
      (node (ref "CN700") (pin "256") (pinfunction "256_256") (pintype "passive"))
    )
    (net (code "168") (name "unconnected-(CN700-Pad257)") (class "Default")
      (node (ref "CN700") (pin "257") (pinfunction "257_257") (pintype "passive"))
    )
    (net (code "169") (name "unconnected-(CN700-Pad258)") (class "Default")
      (node (ref "CN700") (pin "258") (pinfunction "258_258") (pintype "passive"))
    )
  )
)
